# ADCMP607-TDR-head.net
KiCad netlist of a schematic drawn in EAGLE
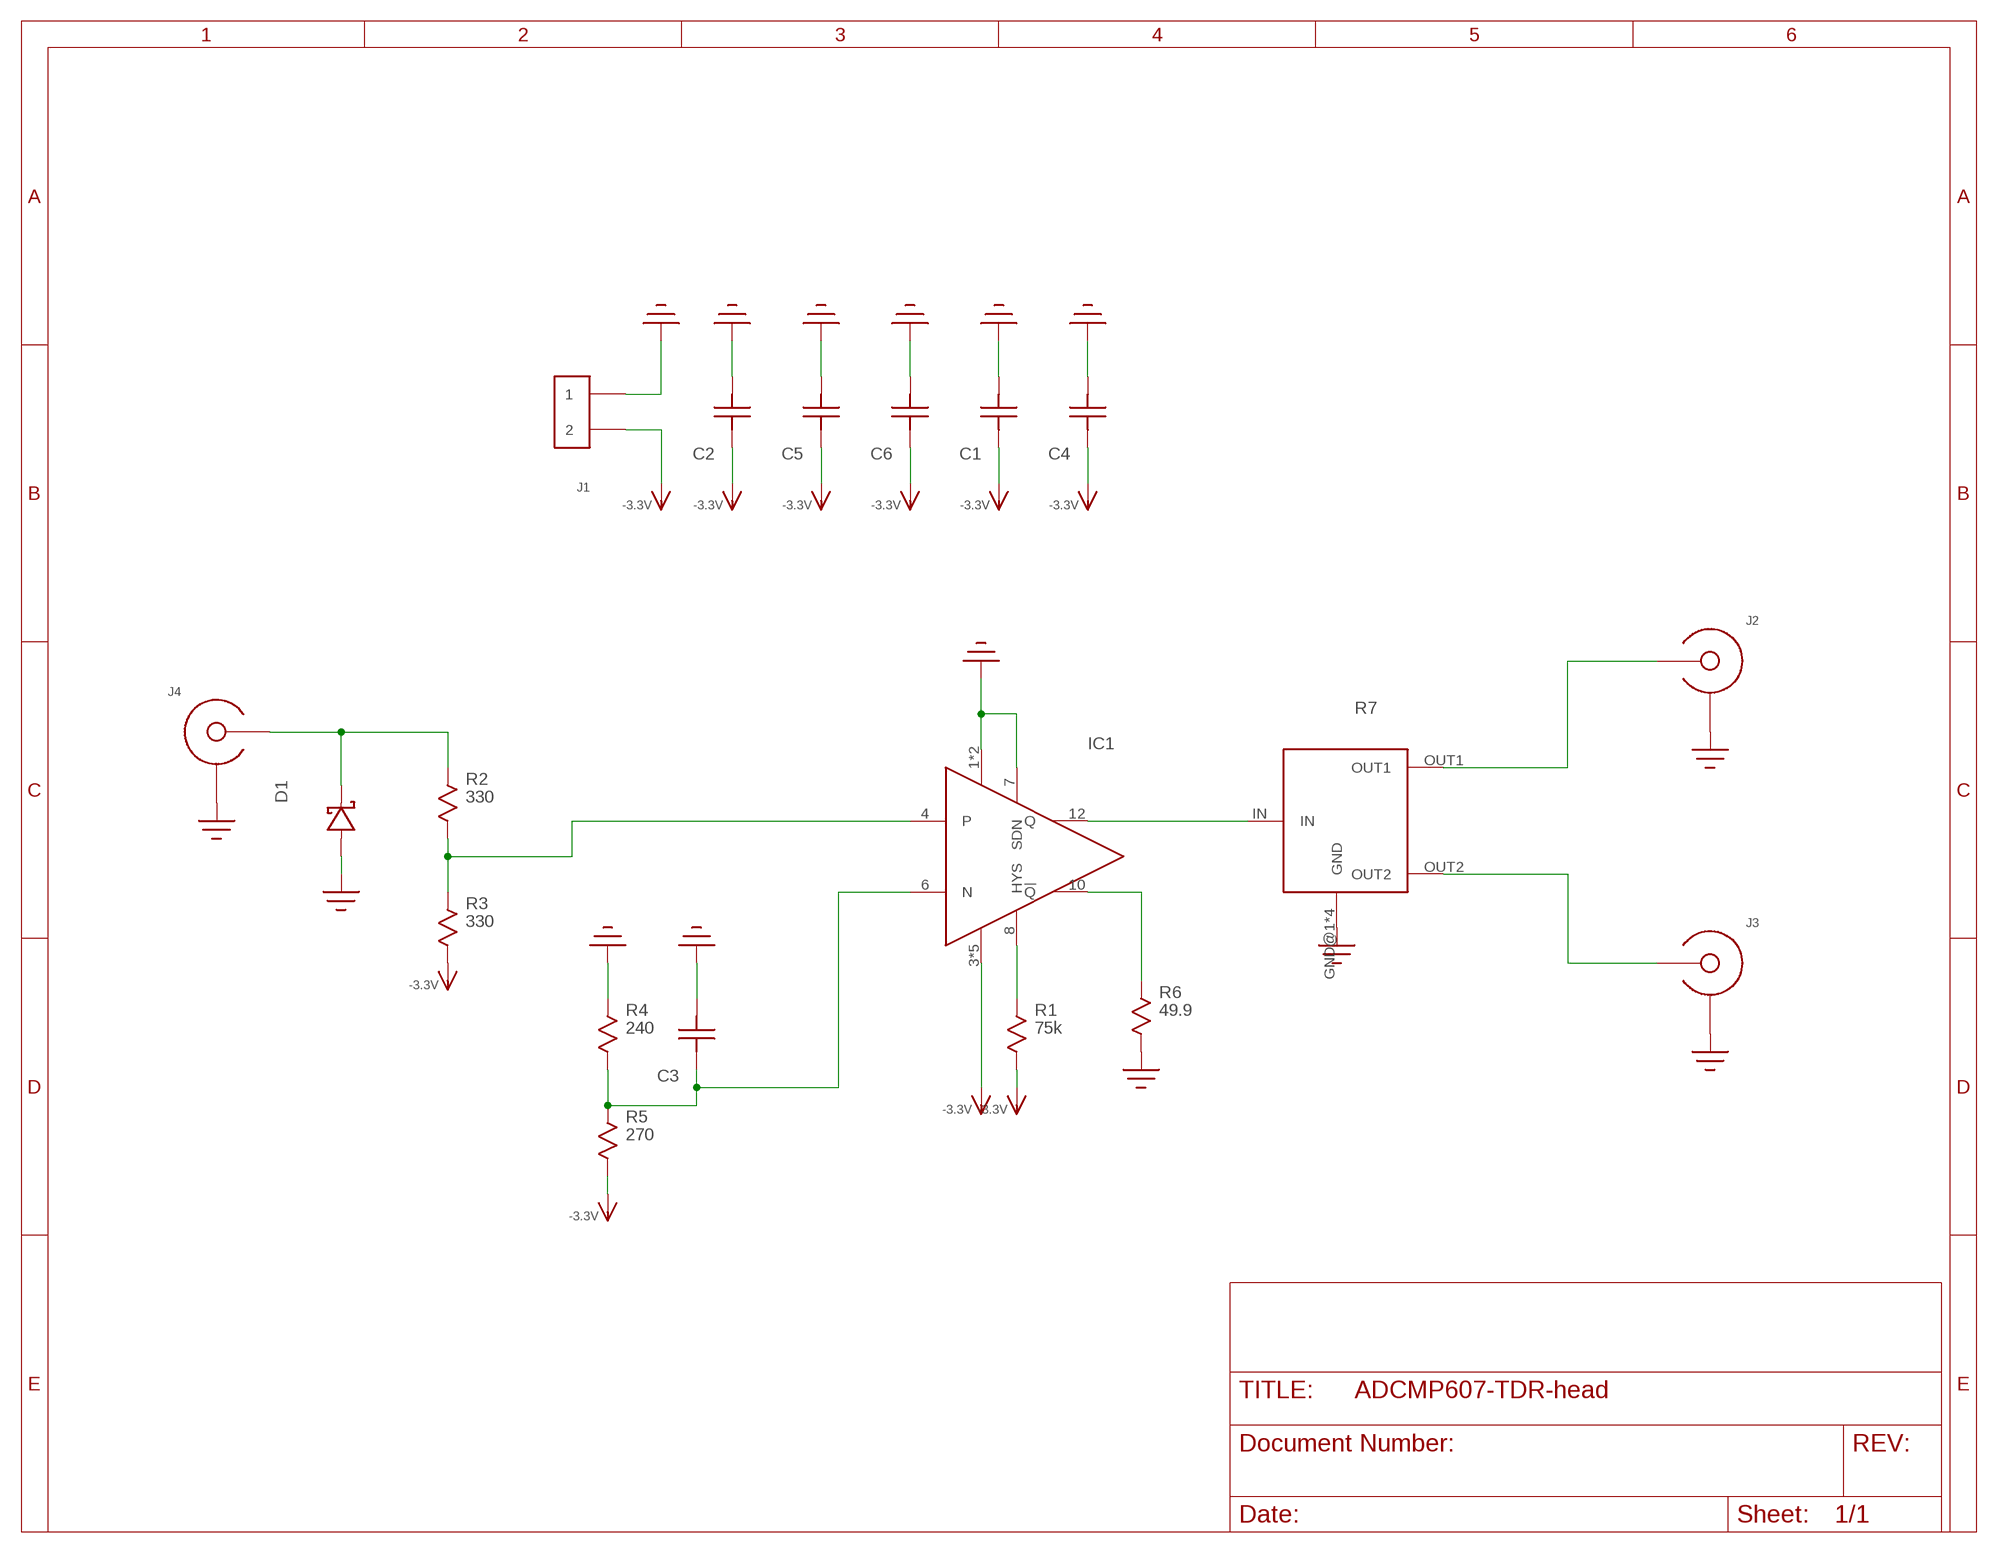
[diagram p0: schematic, sheet 1]

(export (version "E")
  (design (tool "Eeschema 10.0.6"))
  (components
    (comp (ref "C1")
      (value "C0603")
      (footprint "eagle-import:C0603")
      (libsource (lib "eagle-import") (part "C0603"))
    )
    (comp (ref "C2")
      (value "C1206")
      (footprint "eagle-import:1206")
      (libsource (lib "eagle-import") (part "C1206"))
    )
    (comp (ref "C3")
      (value "C0603")
      (footprint "eagle-import:C0603")
      (libsource (lib "eagle-import") (part "C0603"))
    )
    (comp (ref "C4")
      (value "C0603")
      (footprint "eagle-import:C0603")
      (libsource (lib "eagle-import") (part "C0603"))
    )
    (comp (ref "C5")
      (value "C0603")
      (footprint "eagle-import:C0603")
      (libsource (lib "eagle-import") (part "C0603"))
    )
    (comp (ref "C6")
      (value "C0603")
      (footprint "eagle-import:C0603")
      (libsource (lib "eagle-import") (part "C0603"))
    )
    (comp (ref "D1")
      (value "SCHOTTKYSOT-23")
      (footprint "eagle-import:SOT-23")
      (libsource (lib "eagle-import") (part "SCHOTTKYSOT-23"))
    )
    (comp (ref "IC1")
      (value "ADCMP607")
      (footprint "eagle-import:QFN12-3X3")
      (libsource (lib "eagle-import") (part "ADCMP607"))
    )
    (comp (ref "J1")
      (value "HEADER_2PIN")
      (footprint "eagle-import:HEADER_2PIN")
      (libsource (lib "eagle-import") (part "HEADER_2PIN"))
    )
    (comp (ref "J2")
      (value "SMA-EDGE-LAUNCH4020_TAPER")
      (footprint "eagle-import:SMA_EDGE_LAUNCH_2L_4020_TAPER")
      (libsource (lib "eagle-import") (part "SMA-EDGE-LAUNCH4020_TAPER"))
    )
    (comp (ref "J3")
      (value "SMA-EDGE-LAUNCH4020_TAPER")
      (footprint "eagle-import:SMA_EDGE_LAUNCH_2L_4020_TAPER")
      (libsource (lib "eagle-import") (part "SMA-EDGE-LAUNCH4020_TAPER"))
    )
    (comp (ref "J4")
      (value "SMA-EDGE-LAUNCH4020_TAPER")
      (footprint "eagle-import:SMA_EDGE_LAUNCH_2L_4020_TAPER")
      (libsource (lib "eagle-import") (part "SMA-EDGE-LAUNCH4020_TAPER"))
    )
    (comp (ref "R1")
      (value "75k")
      (footprint "eagle-import:R0603")
      (libsource (lib "eagle-import") (part "R0603"))
    )
    (comp (ref "R2")
      (value "330")
      (footprint "eagle-import:R0603")
      (libsource (lib "eagle-import") (part "R0603"))
    )
    (comp (ref "R3")
      (value "330")
      (footprint "eagle-import:R0603")
      (libsource (lib "eagle-import") (part "R0603"))
    )
    (comp (ref "R4")
      (value "240")
      (footprint "eagle-import:R0603")
      (libsource (lib "eagle-import") (part "R0603"))
    )
    (comp (ref "R5")
      (value "270")
      (footprint "eagle-import:R0603")
      (libsource (lib "eagle-import") (part "R0603"))
    )
    (comp (ref "R6")
      (value "49.9")
      (footprint "eagle-import:0402")
      (libsource (lib "eagle-import") (part "R0402"))
    )
    (comp (ref "R7")
      (value "PS2012G-SPLITTER")
      (footprint "eagle-import:PS2012G-SPLITTER")
      (libsource (lib "eagle-import") (part "PS2012G-SPLITTER"))
    )
  )
  (nets
    (net (code "1") (name "-3.3V") (class "Default")
      (node (ref "C1") (pin "P$2") (pinfunction "P$2_P$2") (pintype "bidirectional"))
      (node (ref "C2") (pin "P$2") (pinfunction "P$2_P$2") (pintype "bidirectional"))
      (node (ref "C4") (pin "P$2") (pinfunction "P$2_P$2") (pintype "bidirectional"))
      (node (ref "C5") (pin "P$2") (pinfunction "P$2_P$2") (pintype "bidirectional"))
      (node (ref "C6") (pin "P$2") (pinfunction "P$2_P$2") (pintype "bidirectional"))
      (node (ref "IC1") (pin "11") (pinfunction "VEE_11") (pintype "bidirectional"))
      (node (ref "IC1") (pin "3") (pinfunction "VEE_3") (pintype "bidirectional"))
      (node (ref "IC1") (pin "5") (pinfunction "VEE_5") (pintype "bidirectional"))
      (node (ref "IC1") (pin "9") (pinfunction "VEE_9") (pintype "bidirectional"))
      (node (ref "IC1") (pin "EP") (pinfunction "VEE_EP") (pintype "bidirectional"))
      (node (ref "J1") (pin "2") (pinfunction "2_2") (pintype "bidirectional"))
      (node (ref "R1") (pin "P$2") (pinfunction "P$4_P$2") (pintype "bidirectional"))
      (node (ref "R3") (pin "P$2") (pinfunction "P$4_P$2") (pintype "bidirectional"))
      (node (ref "R5") (pin "P$2") (pinfunction "P$4_P$2") (pintype "bidirectional"))
    )
    (net (code "2") (name "GND") (class "Default")
      (node (ref "C1") (pin "P$1") (pinfunction "P$1_P$1") (pintype "bidirectional"))
      (node (ref "C2") (pin "P$1") (pinfunction "P$1_P$1") (pintype "bidirectional"))
      (node (ref "C3") (pin "P$1") (pinfunction "P$1_P$1") (pintype "bidirectional"))
      (node (ref "C4") (pin "P$1") (pinfunction "P$1_P$1") (pintype "bidirectional"))
      (node (ref "C5") (pin "P$1") (pinfunction "P$1_P$1") (pintype "bidirectional"))
      (node (ref "C6") (pin "P$1") (pinfunction "P$1_P$1") (pintype "bidirectional"))
      (node (ref "D1") (pin "1") (pinfunction "ANODE_1") (pintype "bidirectional"))
      (node (ref "IC1") (pin "1") (pinfunction "VCC_1") (pintype "bidirectional"))
      (node (ref "IC1") (pin "2") (pinfunction "VCC_2") (pintype "bidirectional"))
      (node (ref "IC1") (pin "7") (pinfunction "SDN_7") (pintype "bidirectional"))
      (node (ref "J1") (pin "1") (pinfunction "1_1") (pintype "bidirectional"))
      (node (ref "J2") (pin "BOTTOM_GND") (pinfunction "SHIELD_BOTTOM_GND") (pintype "bidirectional"))
      (node (ref "J2") (pin "GND@1") (pinfunction "SHIELD_GND@1") (pintype "bidirectional"))
      (node (ref "J2") (pin "GND@14") (pinfunction "SHIELD_GND@14") (pintype "bidirectional"))
      (node (ref "J2") (pin "GND@15") (pinfunction "SHIELD_GND@15") (pintype "bidirectional"))
      (node (ref "J2") (pin "GND@16") (pinfunction "SHIELD_GND@16") (pintype "bidirectional"))
      (node (ref "J2") (pin "GND@17") (pinfunction "SHIELD_GND@17") (pintype "bidirectional"))
      (node (ref "J2") (pin "GND@2") (pinfunction "SHIELD_GND@2") (pintype "bidirectional"))
      (node (ref "J2") (pin "GND@3") (pinfunction "SHIELD_GND@3") (pintype "bidirectional"))
      (node (ref "J2") (pin "GND@4") (pinfunction "SHIELD_GND@4") (pintype "bidirectional"))
      (node (ref "J2") (pin "GND@5") (pinfunction "SHIELD_GND@5") (pintype "bidirectional"))
      (node (ref "J2") (pin "GND@6") (pinfunction "SHIELD_GND@6") (pintype "bidirectional"))
      (node (ref "J2") (pin "GND@7") (pinfunction "SHIELD_GND@7") (pintype "bidirectional"))
      (node (ref "J2") (pin "GND@8") (pinfunction "SHIELD_GND@8") (pintype "bidirectional"))
      (node (ref "J2") (pin "GND_PAD1") (pinfunction "SHIELD_GND_PAD1") (pintype "bidirectional"))
      (node (ref "J2") (pin "GND_PAD2") (pinfunction "SHIELD_GND_PAD2") (pintype "bidirectional"))
      (node (ref "J2") (pin "P$1") (pinfunction "SHIELD_P$1") (pintype "bidirectional"))
      (node (ref "J2") (pin "P$2") (pinfunction "SHIELD_P$2") (pintype "bidirectional"))
      (node (ref "J3") (pin "BOTTOM_GND") (pinfunction "SHIELD_BOTTOM_GND") (pintype "bidirectional"))
      (node (ref "J3") (pin "GND@1") (pinfunction "SHIELD_GND@1") (pintype "bidirectional"))
      (node (ref "J3") (pin "GND@14") (pinfunction "SHIELD_GND@14") (pintype "bidirectional"))
      (node (ref "J3") (pin "GND@15") (pinfunction "SHIELD_GND@15") (pintype "bidirectional"))
      (node (ref "J3") (pin "GND@16") (pinfunction "SHIELD_GND@16") (pintype "bidirectional"))
      (node (ref "J3") (pin "GND@17") (pinfunction "SHIELD_GND@17") (pintype "bidirectional"))
      (node (ref "J3") (pin "GND@2") (pinfunction "SHIELD_GND@2") (pintype "bidirectional"))
      (node (ref "J3") (pin "GND@3") (pinfunction "SHIELD_GND@3") (pintype "bidirectional"))
      (node (ref "J3") (pin "GND@4") (pinfunction "SHIELD_GND@4") (pintype "bidirectional"))
      (node (ref "J3") (pin "GND@5") (pinfunction "SHIELD_GND@5") (pintype "bidirectional"))
      (node (ref "J3") (pin "GND@6") (pinfunction "SHIELD_GND@6") (pintype "bidirectional"))
      (node (ref "J3") (pin "GND@7") (pinfunction "SHIELD_GND@7") (pintype "bidirectional"))
      (node (ref "J3") (pin "GND@8") (pinfunction "SHIELD_GND@8") (pintype "bidirectional"))
      (node (ref "J3") (pin "GND_PAD1") (pinfunction "SHIELD_GND_PAD1") (pintype "bidirectional"))
      (node (ref "J3") (pin "GND_PAD2") (pinfunction "SHIELD_GND_PAD2") (pintype "bidirectional"))
      (node (ref "J3") (pin "P$1") (pinfunction "SHIELD_P$1") (pintype "bidirectional"))
      (node (ref "J3") (pin "P$2") (pinfunction "SHIELD_P$2") (pintype "bidirectional"))
      (node (ref "J4") (pin "BOTTOM_GND") (pinfunction "SHIELD_BOTTOM_GND") (pintype "bidirectional"))
      (node (ref "J4") (pin "GND@1") (pinfunction "SHIELD_GND@1") (pintype "bidirectional"))
      (node (ref "J4") (pin "GND@14") (pinfunction "SHIELD_GND@14") (pintype "bidirectional"))
      (node (ref "J4") (pin "GND@15") (pinfunction "SHIELD_GND@15") (pintype "bidirectional"))
      (node (ref "J4") (pin "GND@16") (pinfunction "SHIELD_GND@16") (pintype "bidirectional"))
      (node (ref "J4") (pin "GND@17") (pinfunction "SHIELD_GND@17") (pintype "bidirectional"))
      (node (ref "J4") (pin "GND@2") (pinfunction "SHIELD_GND@2") (pintype "bidirectional"))
      (node (ref "J4") (pin "GND@3") (pinfunction "SHIELD_GND@3") (pintype "bidirectional"))
      (node (ref "J4") (pin "GND@4") (pinfunction "SHIELD_GND@4") (pintype "bidirectional"))
      (node (ref "J4") (pin "GND@5") (pinfunction "SHIELD_GND@5") (pintype "bidirectional"))
      (node (ref "J4") (pin "GND@6") (pinfunction "SHIELD_GND@6") (pintype "bidirectional"))
      (node (ref "J4") (pin "GND@7") (pinfunction "SHIELD_GND@7") (pintype "bidirectional"))
      (node (ref "J4") (pin "GND@8") (pinfunction "SHIELD_GND@8") (pintype "bidirectional"))
      (node (ref "J4") (pin "GND_PAD1") (pinfunction "SHIELD_GND_PAD1") (pintype "bidirectional"))
      (node (ref "J4") (pin "GND_PAD2") (pinfunction "SHIELD_GND_PAD2") (pintype "bidirectional"))
      (node (ref "J4") (pin "P$1") (pinfunction "SHIELD_P$1") (pintype "bidirectional"))
      (node (ref "J4") (pin "P$2") (pinfunction "SHIELD_P$2") (pintype "bidirectional"))
      (node (ref "R4") (pin "P$1") (pinfunction "P$3_P$1") (pintype "bidirectional"))
      (node (ref "R6") (pin "2") (pinfunction "P$4_2") (pintype "bidirectional"))
      (node (ref "R7") (pin "GND@1") (pinfunction "GND_GND@1") (pintype "bidirectional"))
      (node (ref "R7") (pin "GND@2") (pinfunction "GND_GND@2") (pintype "bidirectional"))
      (node (ref "R7") (pin "GND@3") (pinfunction "GND_GND@3") (pintype "bidirectional"))
      (node (ref "R7") (pin "GND@4") (pinfunction "GND_GND@4") (pintype "bidirectional"))
    )
    (net (code "3") (name "Net-(D1-CATHODE)") (class "Default")
      (node (ref "D1") (pin "3") (pinfunction "CATHODE_3") (pintype "bidirectional"))
      (node (ref "J4") (pin "CENTER@1") (pinfunction "CENTER_CENTER@1") (pintype "bidirectional"))
      (node (ref "R2") (pin "P$1") (pinfunction "P$3_P$1") (pintype "bidirectional"))
    )
    (net (code "4") (name "Net-(IC1-HYS)") (class "Default")
      (node (ref "IC1") (pin "8") (pinfunction "HYS_8") (pintype "bidirectional"))
      (node (ref "R1") (pin "P$1") (pinfunction "P$3_P$1") (pintype "bidirectional"))
    )
    (net (code "5") (name "Net-(IC1-N)") (class "Default")
      (node (ref "C3") (pin "P$2") (pinfunction "P$2_P$2") (pintype "bidirectional"))
      (node (ref "IC1") (pin "6") (pinfunction "N_6") (pintype "bidirectional"))
      (node (ref "R4") (pin "P$2") (pinfunction "P$4_P$2") (pintype "bidirectional"))
      (node (ref "R5") (pin "P$1") (pinfunction "P$3_P$1") (pintype "bidirectional"))
    )
    (net (code "6") (name "Net-(IC1-P)") (class "Default")
      (node (ref "IC1") (pin "4") (pinfunction "P_4") (pintype "bidirectional"))
      (node (ref "R2") (pin "P$2") (pinfunction "P$4_P$2") (pintype "bidirectional"))
      (node (ref "R3") (pin "P$1") (pinfunction "P$3_P$1") (pintype "bidirectional"))
    )
    (net (code "7") (name "Net-(IC1-Q)") (class "Default")
      (node (ref "IC1") (pin "12") (pinfunction "Q_12") (pintype "bidirectional"))
      (node (ref "R7") (pin "IN") (pinfunction "IN_IN") (pintype "bidirectional"))
    )
    (net (code "8") (name "Net-(IC1-~{Q})") (class "Default")
      (node (ref "IC1") (pin "10") (pinfunction "~{Q}_10") (pintype "bidirectional"))
      (node (ref "R6") (pin "1") (pinfunction "P$3_1") (pintype "bidirectional"))
    )
    (net (code "9") (name "Net-(J2-CENTER)") (class "Default")
      (node (ref "J2") (pin "CENTER@1") (pinfunction "CENTER_CENTER@1") (pintype "bidirectional"))
      (node (ref "R7") (pin "OUT1") (pinfunction "OUT1_OUT1") (pintype "bidirectional"))
    )
    (net (code "10") (name "Net-(J3-CENTER)") (class "Default")
      (node (ref "J3") (pin "CENTER@1") (pinfunction "CENTER_CENTER@1") (pintype "bidirectional"))
      (node (ref "R7") (pin "OUT2") (pinfunction "OUT2_OUT2") (pintype "bidirectional"))
    )
  )
)
